# LPmini-Prototype_1_4.net
KiCad netlist of a schematic drawn in EAGLE
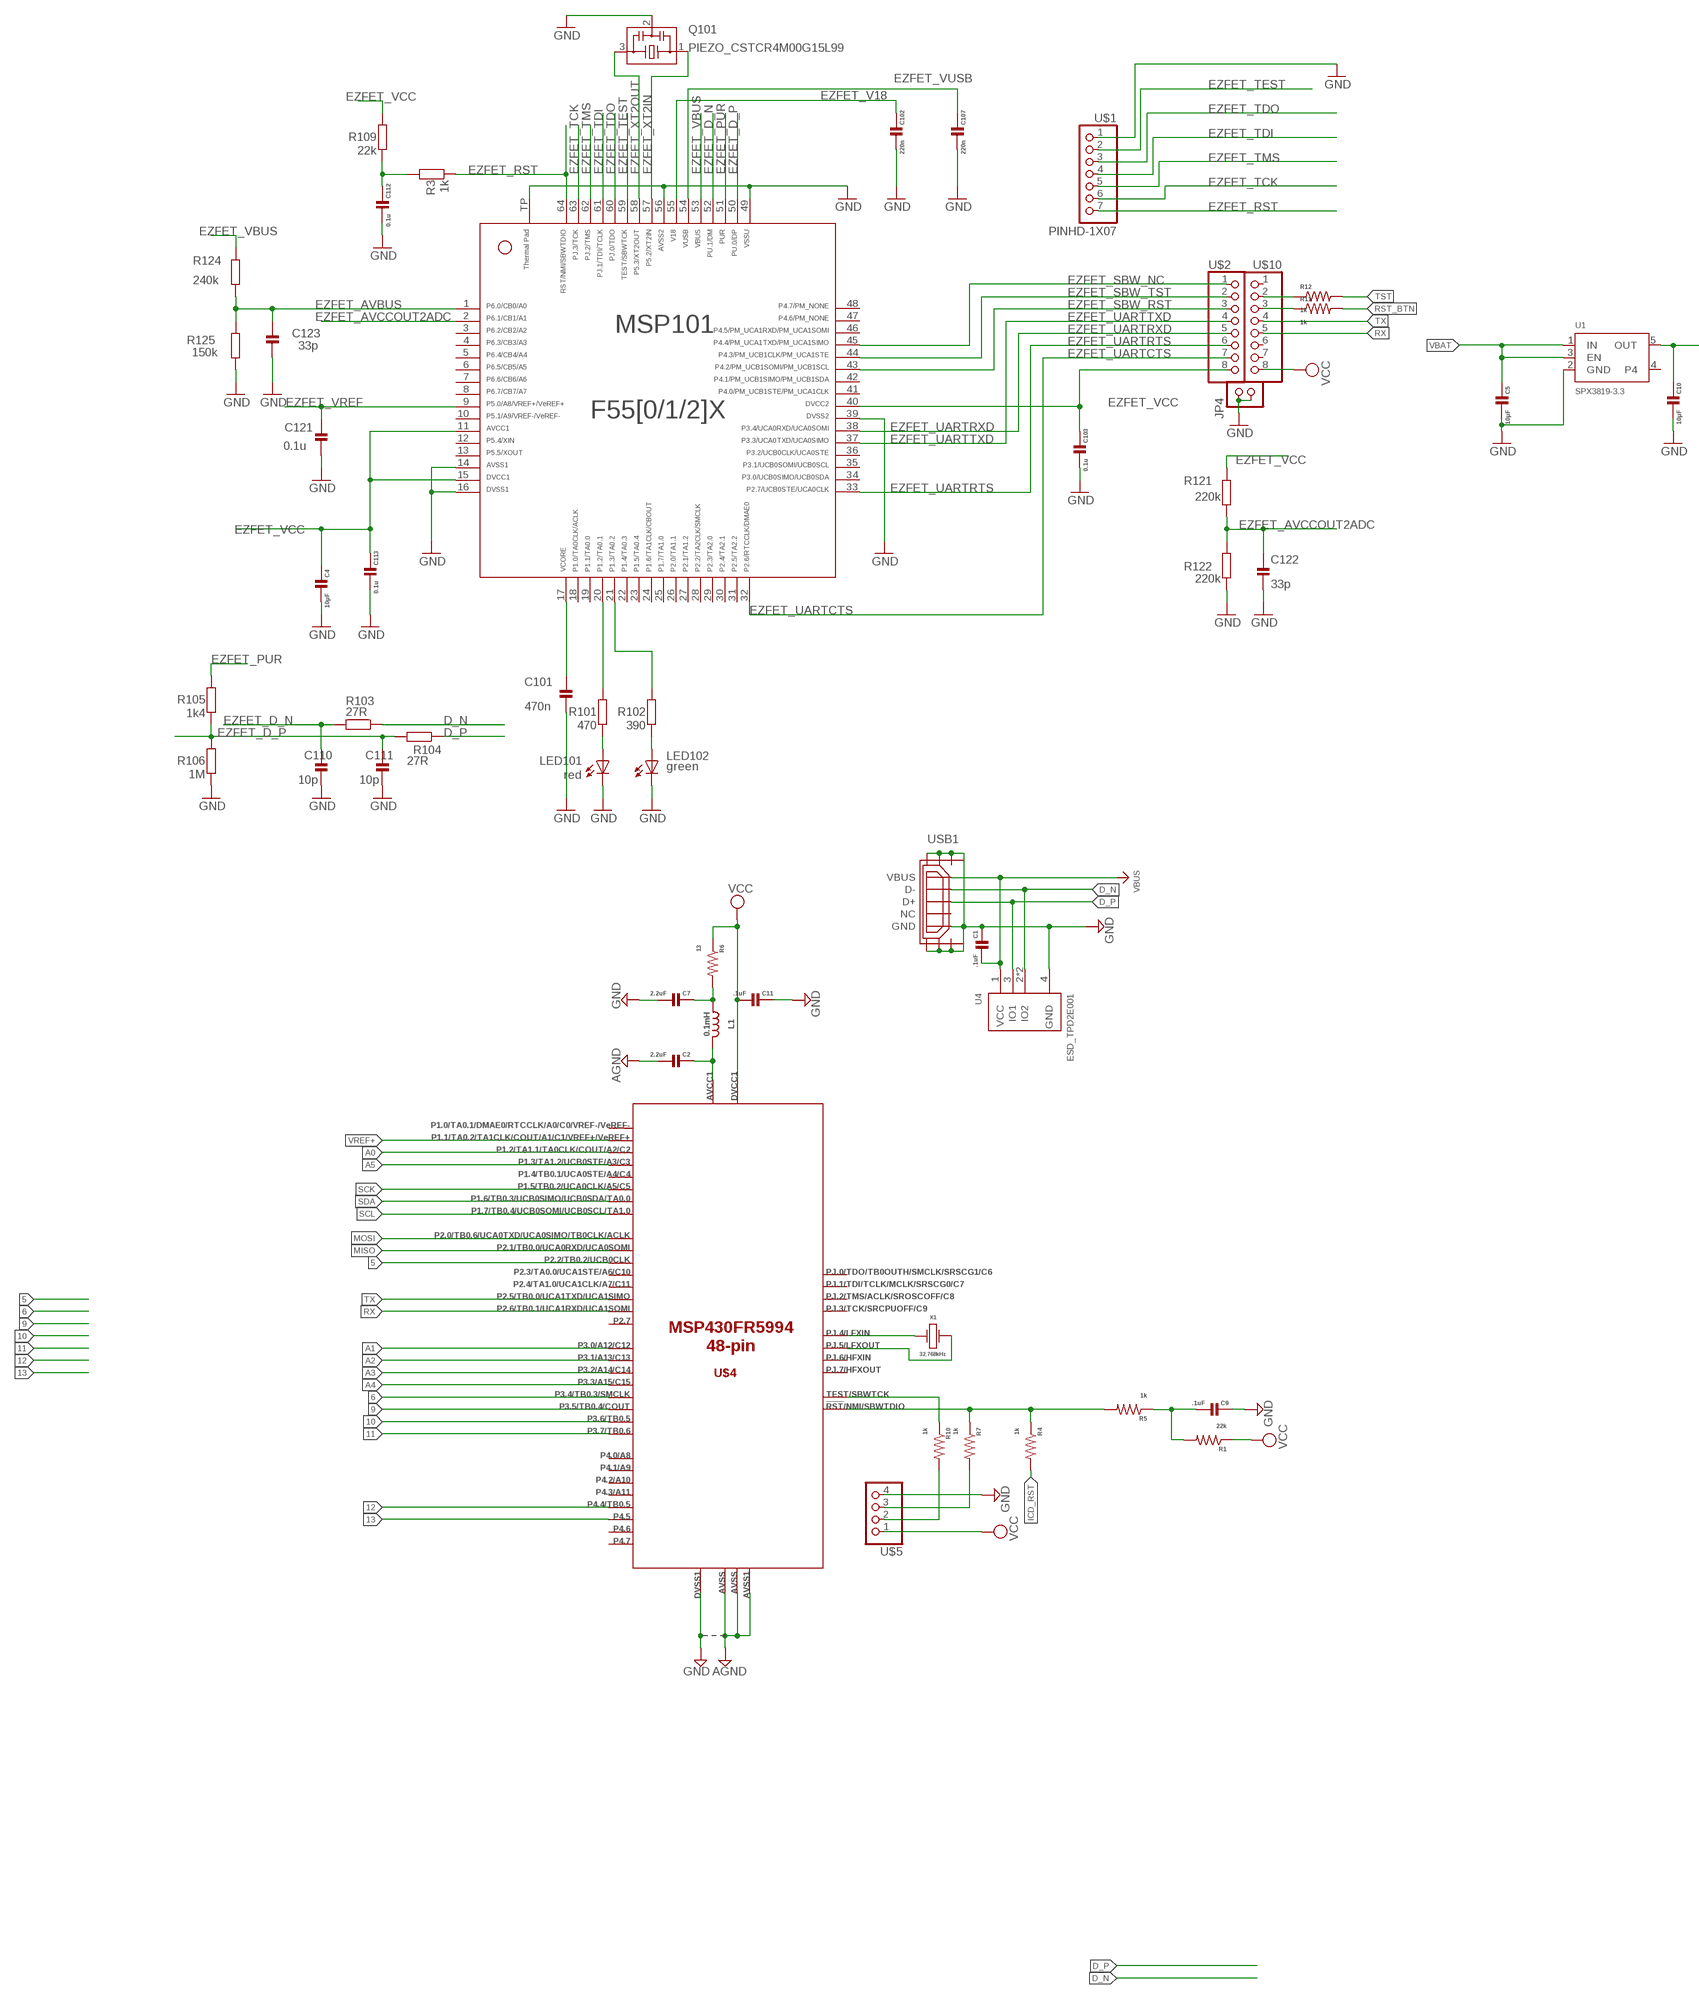
[diagram p0: schematic, sheet 1, part 1 of 2]
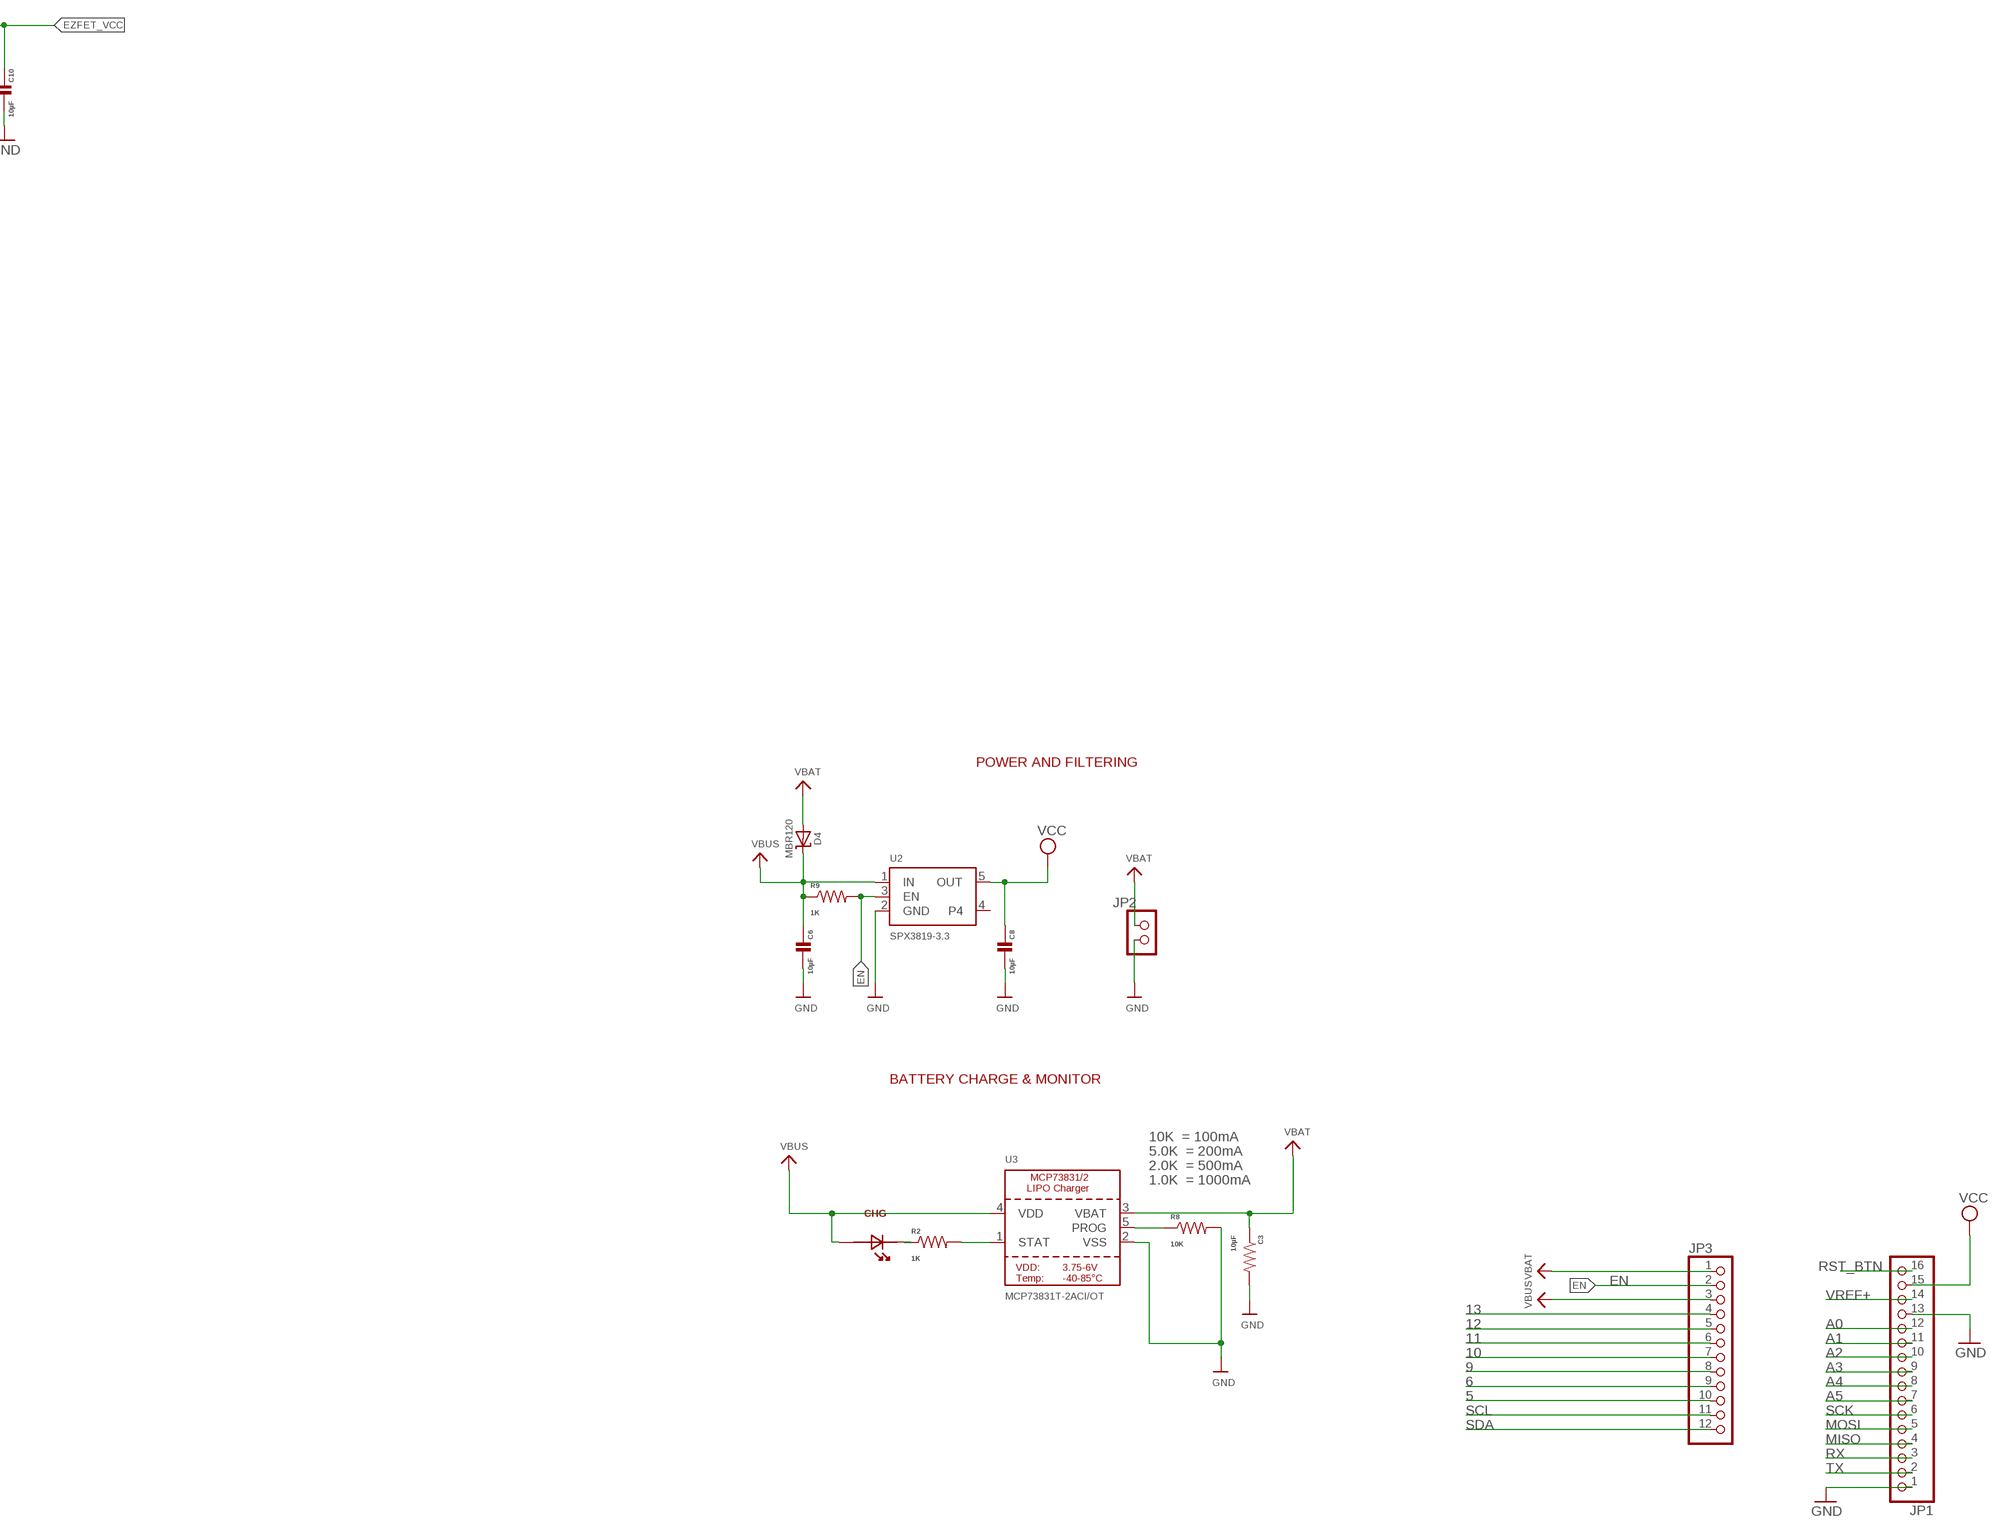
[diagram p1: schematic, sheet 1, part 2 of 2]

(export (version "E")
  (design (tool "Eeschema 10.0.6"))
  (components
    (comp (ref "C1")
      (value ".1uF")
      (footprint "eagle-import:C0402")
      (libsource (lib "eagle-import") (part "C-EUC0402"))
    )
    (comp (ref "C2")
      (value "2.2uF")
      (footprint "eagle-import:C0603")
      (libsource (lib "eagle-import") (part "C-EUC0603"))
    )
    (comp (ref "C3")
      (value "10µF")
      (footprint "eagle-import:R0402")
      (libsource (lib "eagle-import") (part "R-US_R0402"))
    )
    (comp (ref "C4")
      (value "10µF")
      (footprint "eagle-import:C0603")
      (libsource (lib "eagle-import") (part "C-EUC0603"))
    )
    (comp (ref "C5")
      (value "10µF")
      (footprint "eagle-import:C0603")
      (libsource (lib "eagle-import") (part "C-EUC0603"))
    )
    (comp (ref "C6")
      (value "10µF")
      (footprint "eagle-import:C0603")
      (libsource (lib "eagle-import") (part "C-EUC0603"))
    )
    (comp (ref "C7")
      (value "2.2uF")
      (footprint "eagle-import:C0603")
      (libsource (lib "eagle-import") (part "C-EUC0603"))
    )
    (comp (ref "C8")
      (value "10µF")
      (footprint "eagle-import:C0603")
      (libsource (lib "eagle-import") (part "C-EUC0603"))
    )
    (comp (ref "C9")
      (value ".1uF")
      (footprint "eagle-import:C0402")
      (libsource (lib "eagle-import") (part "C-EUC0402"))
    )
    (comp (ref "C10")
      (value "10µF")
      (footprint "eagle-import:C0603")
      (libsource (lib "eagle-import") (part "C-EUC0603"))
    )
    (comp (ref "C11")
      (value ".1uF")
      (footprint "eagle-import:C0402")
      (libsource (lib "eagle-import") (part "C-EUC0402"))
    )
    (comp (ref "C101")
      (value "470n")
      (footprint "eagle-import:C0402")
      (libsource (lib "eagle-import") (part "C-EUC0402"))
    )
    (comp (ref "C102")
      (value "220n")
      (footprint "eagle-import:C0402")
      (libsource (lib "eagle-import") (part "C-EUC0402"))
    )
    (comp (ref "C103")
      (value "0.1u")
      (footprint "eagle-import:C0402")
      (libsource (lib "eagle-import") (part "C-EUC0402"))
    )
    (comp (ref "C107")
      (value "220n")
      (footprint "eagle-import:C0402")
      (libsource (lib "eagle-import") (part "C-EUC0402"))
    )
    (comp (ref "C110")
      (value "10p")
      (footprint "eagle-import:C0402")
      (libsource (lib "eagle-import") (part "C-EUC0402"))
    )
    (comp (ref "C111")
      (value "10p")
      (footprint "eagle-import:C0402")
      (libsource (lib "eagle-import") (part "C-EUC0402"))
    )
    (comp (ref "C112")
      (value "0.1u")
      (footprint "eagle-import:C0402")
      (libsource (lib "eagle-import") (part "C-EUC0402"))
    )
    (comp (ref "C113")
      (value "0.1u")
      (footprint "eagle-import:C0402")
      (libsource (lib "eagle-import") (part "C-EUC0402"))
    )
    (comp (ref "C121")
      (value "0.1u")
      (footprint "eagle-import:C0402")
      (libsource (lib "eagle-import") (part "C-EUC0402"))
    )
    (comp (ref "C122")
      (value "33p")
      (footprint "eagle-import:C0402")
      (libsource (lib "eagle-import") (part "C-EUC0402"))
    )
    (comp (ref "C123")
      (value "33p")
      (footprint "eagle-import:C0402")
      (libsource (lib "eagle-import") (part "C-EUC0402"))
    )
    (comp (ref "CHG")
      (value "ORANGE")
      (footprint "eagle-import:LED_0603")
      (libsource (lib "eagle-import") (part "LED0603"))
    )
    (comp (ref "D4")
      (value "MBR120")
      (footprint "eagle-import:SOD-123")
      (libsource (lib "eagle-import") (part "DIODE-SCHOTTKYSOD-123"))
    )
    (comp (ref "JP1")
      (value "HEADER-1X16ROUND")
      (footprint "eagle-import:1X16_ROUND")
      (libsource (lib "eagle-import") (part "HEADER-1X16ROUND"))
    )
    (comp (ref "JP2")
      (value "0_JOSEPH_PINHD-1X2END")
      (footprint "eagle-import:0_JOSEPH_1X02-END")
      (libsource (lib "eagle-import") (part "0_JOSEPH_PINHD-1X2END"))
    )
    (comp (ref "JP3")
      (value "HEADER-1X12")
      (footprint "eagle-import:1X12_ROUND")
      (libsource (lib "eagle-import") (part "HEADER-1X12"))
    )
    (comp (ref "JP4")
      (value "0_JOSEPH_PINHD-1X2SMALL")
      (footprint "eagle-import:0_JOSEPH_1X02-SMALL")
      (libsource (lib "eagle-import") (part "0_JOSEPH_PINHD-1X2SMALL"))
    )
    (comp (ref "L1")
      (value "0.1mH")
      (footprint "eagle-import:RCL_R0805")
      (libsource (lib "eagle-import") (part "SMD_INDUCT0805"))
    )
    (comp (ref "LED101")
      (value "red")
      (footprint "eagle-import:CHIP-LED0603")
      (libsource (lib "eagle-import") (part "LEDCHIP-LED0603"))
    )
    (comp (ref "LED102")
      (value "green")
      (footprint "eagle-import:CHIP-LED0603")
      (libsource (lib "eagle-import") (part "LEDCHIP-LED0603"))
    )
    (comp (ref "MSP101")
      (value "MSP430F5528IRGC")
      (footprint "eagle-import:RGC64")
      (libsource (lib "eagle-import") (part "F55[0/1/2]X---RGC64"))
    )
    (comp (ref "Q101")
      (value "PIEZO_CSTCR4M00G15L99")
      (footprint "eagle-import:MURATA-FILTER_CSTCR")
      (fields (field (name "MPN") "CSTCR6M00G53-R0"))
      (libsource (lib "eagle-import") (part "MURATA-FILTER_CSTCR6M00G53Z"))
    )
    (comp (ref "R1")
      (value "22k")
      (footprint "eagle-import:R0402")
      (libsource (lib "eagle-import") (part "R-US_R0402"))
    )
    (comp (ref "R2")
      (value "1K")
      (footprint "eagle-import:R0402")
      (libsource (lib "eagle-import") (part "R-US_R0402"))
    )
    (comp (ref "R3")
      (value "1k")
      (footprint "eagle-import:R0402")
      (libsource (lib "eagle-import") (part "R-EU_R0402"))
    )
    (comp (ref "R4")
      (value "1k")
      (footprint "eagle-import:R0402")
      (libsource (lib "eagle-import") (part "R-US_R0402"))
    )
    (comp (ref "R5")
      (value "1k")
      (footprint "eagle-import:R0402")
      (libsource (lib "eagle-import") (part "R-US_R0402"))
    )
    (comp (ref "R6")
      (value "13")
      (footprint "eagle-import:R0402")
      (libsource (lib "eagle-import") (part "R-US_R0402"))
    )
    (comp (ref "R7")
      (value "1k")
      (footprint "eagle-import:R0402")
      (libsource (lib "eagle-import") (part "R-US_R0402"))
    )
    (comp (ref "R8")
      (value "10K")
      (footprint "eagle-import:R0402")
      (libsource (lib "eagle-import") (part "R-US_R0402"))
    )
    (comp (ref "R9")
      (value "1K")
      (footprint "eagle-import:R0402")
      (libsource (lib "eagle-import") (part "R-US_R0402"))
    )
    (comp (ref "R10")
      (value "1k")
      (footprint "eagle-import:R0402")
      (libsource (lib "eagle-import") (part "R-US_R0402"))
    )
    (comp (ref "R11")
      (value "1k")
      (footprint "eagle-import:R0402")
      (libsource (lib "eagle-import") (part "R-US_R0402"))
    )
    (comp (ref "R12")
      (value "1k")
      (footprint "eagle-import:R0402")
      (libsource (lib "eagle-import") (part "R-US_R0402"))
    )
    (comp (ref "R101")
      (value "470")
      (footprint "eagle-import:R0402")
      (libsource (lib "eagle-import") (part "R-EU_R0402"))
    )
    (comp (ref "R102")
      (value "390")
      (footprint "eagle-import:R0402")
      (libsource (lib "eagle-import") (part "R-EU_R0402"))
    )
    (comp (ref "R103")
      (value "27R")
      (footprint "eagle-import:R0402")
      (libsource (lib "eagle-import") (part "R-EU_R0402"))
    )
    (comp (ref "R104")
      (value "27R")
      (footprint "eagle-import:R0402")
      (libsource (lib "eagle-import") (part "R-EU_R0402"))
    )
    (comp (ref "R105")
      (value "1k4")
      (footprint "eagle-import:R0402")
      (libsource (lib "eagle-import") (part "R-EU_R0402"))
    )
    (comp (ref "R106")
      (value "1M")
      (footprint "eagle-import:R0402")
      (libsource (lib "eagle-import") (part "R-EU_R0402"))
    )
    (comp (ref "R109")
      (value "22k")
      (footprint "eagle-import:R0402")
      (libsource (lib "eagle-import") (part "R-EU_R0402"))
    )
    (comp (ref "R121")
      (value "220k")
      (footprint "eagle-import:R0402")
      (libsource (lib "eagle-import") (part "R-EU_R0402"))
    )
    (comp (ref "R122")
      (value "220k")
      (footprint "eagle-import:R0402")
      (libsource (lib "eagle-import") (part "R-EU_R0402"))
    )
    (comp (ref "R124")
      (value "240k")
      (footprint "eagle-import:R0402")
      (libsource (lib "eagle-import") (part "R-EU_R0402"))
    )
    (comp (ref "R125")
      (value "150k")
      (footprint "eagle-import:R0402")
      (libsource (lib "eagle-import") (part "R-EU_R0402"))
    )
    (comp (ref "U$1")
      (value "PINHD-1X07")
      (footprint "eagle-import:1X07")
      (libsource (lib "eagle-import") (part "PINHD-1X07"))
    )
    (comp (ref "U$2")
      (value "PINHD-1X08SMALL")
      (footprint "eagle-import:1X08-SMALL")
      (libsource (lib "eagle-import") (part "PINHD-1X08SMALL"))
    )
    (comp (ref "U$4")
      (value "MSP430FR5994-48PIN")
      (footprint "eagle-import:48QFN")
      (libsource (lib "eagle-import") (part "MSP430FR5994-48PIN"))
    )
    (comp (ref "U$5")
      (value "PINHD_1X4")
      (footprint "eagle-import:1X04")
      (libsource (lib "eagle-import") (part "PINHD_1X4"))
    )
    (comp (ref "U$10")
      (value "PINHD-1X08SMALL")
      (footprint "eagle-import:1X08-SMALL")
      (libsource (lib "eagle-import") (part "PINHD-1X08SMALL"))
    )
    (comp (ref "U1")
      (value "SPX3819-3.3")
      (footprint "eagle-import:SOT23-5")
      (libsource (lib "eagle-import") (part "VREG_SOT23-5"))
    )
    (comp (ref "U2")
      (value "SPX3819-3.3")
      (footprint "eagle-import:SOT23-5")
      (libsource (lib "eagle-import") (part "VREG_SOT23-5"))
    )
    (comp (ref "U3")
      (value "MCP73831T-2ACI/OT")
      (footprint "eagle-import:SOT23-5")
      (libsource (lib "eagle-import") (part "MCP73831/2"))
    )
    (comp (ref "U4")
      (value "ESD_TPD2E001")
      (footprint "eagle-import:PROJECT7264_TPD2E001-DRL")
      (libsource (lib "eagle-import") (part "ESD_TPD2E001"))
    )
    (comp (ref "USB1")
      (value "USB_CON-UPDATE_USB_MICRO_FLIPPED")
      (footprint "eagle-import:USB_CON-UPDATE_HIROSE-ZX62R-B-5P")
      (libsource (lib "eagle-import") (part "USB_CON-UPDATE_USB_MICRO_FLIPPED"))
    )
    (comp (ref "X1")
      (value "32.768kHz")
      (footprint "eagle-import:CRYSTAL_ABS05")
      (libsource (lib "eagle-import") (part "CRYSTALABS-05"))
    )
  )
  (nets
    (net (code "1") (name "/EZFET_AVBUS") (class "Default")
      (node (ref "C123") (pin "2") (pinfunction "2_2") (pintype "passive"))
      (node (ref "MSP101") (pin "1") (pinfunction "1_1") (pintype "bidirectional"))
      (node (ref "R124") (pin "2") (pinfunction "2_2") (pintype "passive"))
      (node (ref "R125") (pin "1") (pinfunction "1_1") (pintype "passive"))
    )
    (net (code "2") (name "/EZFET_AVCCOUT2ADC") (class "Default")
      (node (ref "C122") (pin "2") (pinfunction "2_2") (pintype "passive"))
      (node (ref "MSP101") (pin "2") (pinfunction "2_2") (pintype "bidirectional"))
      (node (ref "R121") (pin "2") (pinfunction "2_2") (pintype "passive"))
      (node (ref "R122") (pin "1") (pinfunction "1_1") (pintype "passive"))
    )
    (net (code "3") (name "/EZFET_D_N") (class "Default")
      (node (ref "C110") (pin "1") (pinfunction "1_1") (pintype "passive"))
      (node (ref "MSP101") (pin "52") (pinfunction "52_52") (pintype "bidirectional"))
      (node (ref "R103") (pin "2") (pinfunction "2_2") (pintype "passive"))
    )
    (net (code "4") (name "/EZFET_D_P") (class "Default")
      (node (ref "C111") (pin "1") (pinfunction "1_1") (pintype "passive"))
      (node (ref "MSP101") (pin "50") (pinfunction "50_50") (pintype "bidirectional"))
      (node (ref "R104") (pin "2") (pinfunction "2_2") (pintype "passive"))
      (node (ref "R105") (pin "1") (pinfunction "1_1") (pintype "passive"))
      (node (ref "R106") (pin "2") (pinfunction "2_2") (pintype "passive"))
    )
    (net (code "5") (name "/EZFET_PUR") (class "Default")
      (node (ref "MSP101") (pin "51") (pinfunction "51_51") (pintype "bidirectional"))
      (node (ref "R105") (pin "2") (pinfunction "2_2") (pintype "passive"))
    )
    (net (code "6") (name "/EZFET_RST") (class "Default")
      (node (ref "MSP101") (pin "64") (pinfunction "64_64") (pintype "bidirectional"))
      (node (ref "R3") (pin "1") (pinfunction "1_1") (pintype "passive"))
      (node (ref "U$1") (pin "7") (pinfunction "7_7") (pintype "passive"))
    )
    (net (code "7") (name "/EZFET_SBW_NC") (class "Default")
      (node (ref "MSP101") (pin "45") (pinfunction "45_45") (pintype "bidirectional"))
      (node (ref "U$2") (pin "1") (pinfunction "1_1") (pintype "passive"))
    )
    (net (code "8") (name "/EZFET_SBW_RST") (class "Default")
      (node (ref "MSP101") (pin "43") (pinfunction "43_43") (pintype "bidirectional"))
      (node (ref "U$2") (pin "3") (pinfunction "3_3") (pintype "passive"))
    )
    (net (code "9") (name "/EZFET_SBW_TST") (class "Default")
      (node (ref "MSP101") (pin "44") (pinfunction "44_44") (pintype "bidirectional"))
      (node (ref "U$2") (pin "2") (pinfunction "2_2") (pintype "passive"))
    )
    (net (code "10") (name "/EZFET_TCK") (class "Default")
      (node (ref "MSP101") (pin "63") (pinfunction "63_63") (pintype "bidirectional"))
      (node (ref "U$1") (pin "6") (pinfunction "6_6") (pintype "passive"))
    )
    (net (code "11") (name "/EZFET_TDI") (class "Default")
      (node (ref "MSP101") (pin "61") (pinfunction "61_61") (pintype "bidirectional"))
      (node (ref "U$1") (pin "4") (pinfunction "4_4") (pintype "passive"))
    )
    (net (code "12") (name "/EZFET_TDO") (class "Default")
      (node (ref "MSP101") (pin "60") (pinfunction "60_60") (pintype "bidirectional"))
      (node (ref "U$1") (pin "3") (pinfunction "3_3") (pintype "passive"))
    )
    (net (code "13") (name "/EZFET_TEST") (class "Default")
      (node (ref "MSP101") (pin "59") (pinfunction "59_59") (pintype "input"))
      (node (ref "U$1") (pin "2") (pinfunction "2_2") (pintype "passive"))
    )
    (net (code "14") (name "/EZFET_TMS") (class "Default")
      (node (ref "MSP101") (pin "62") (pinfunction "62_62") (pintype "bidirectional"))
      (node (ref "U$1") (pin "5") (pinfunction "5_5") (pintype "passive"))
    )
    (net (code "15") (name "/EZFET_UARTCTS") (class "Default")
      (node (ref "MSP101") (pin "32") (pinfunction "32_32") (pintype "bidirectional"))
      (node (ref "U$2") (pin "7") (pinfunction "7_7") (pintype "passive"))
    )
    (net (code "16") (name "/EZFET_UARTRTS") (class "Default")
      (node (ref "MSP101") (pin "33") (pinfunction "33_33") (pintype "bidirectional"))
      (node (ref "U$2") (pin "6") (pinfunction "6_6") (pintype "passive"))
    )
    (net (code "17") (name "/EZFET_UARTRXD") (class "Default")
      (node (ref "MSP101") (pin "38") (pinfunction "38_38") (pintype "bidirectional"))
      (node (ref "U$2") (pin "5") (pinfunction "5_5") (pintype "passive"))
    )
    (net (code "18") (name "/EZFET_UARTTXD") (class "Default")
      (node (ref "MSP101") (pin "37") (pinfunction "37_37") (pintype "bidirectional"))
      (node (ref "U$2") (pin "4") (pinfunction "4_4") (pintype "passive"))
    )
    (net (code "19") (name "/EZFET_V18") (class "Default")
      (node (ref "C102") (pin "1") (pinfunction "1_1") (pintype "passive"))
      (node (ref "MSP101") (pin "55") (pinfunction "55_55") (pintype "power_in"))
    )
    (net (code "20") (name "/EZFET_VBUS") (class "Default")
      (node (ref "MSP101") (pin "53") (pinfunction "53_53") (pintype "power_in"))
      (node (ref "R124") (pin "1") (pinfunction "1_1") (pintype "passive"))
    )
    (net (code "21") (name "/EZFET_VREF") (class "Default")
      (node (ref "C121") (pin "1") (pinfunction "1_1") (pintype "passive"))
      (node (ref "MSP101") (pin "9") (pinfunction "9_9") (pintype "bidirectional"))
    )
    (net (code "22") (name "/EZFET_VUSB") (class "Default")
      (node (ref "C107") (pin "1") (pinfunction "1_1") (pintype "passive"))
      (node (ref "MSP101") (pin "54") (pinfunction "54_54") (pintype "power_in"))
    )
    (net (code "23") (name "/EZFET_XT2IN") (class "Default")
      (node (ref "MSP101") (pin "57") (pinfunction "57_57") (pintype "bidirectional"))
      (node (ref "Q101") (pin "1") (pinfunction "1_1") (pintype "passive"))
    )
    (net (code "24") (name "/EZFET_XT2OUT") (class "Default")
      (node (ref "MSP101") (pin "58") (pinfunction "58_58") (pintype "bidirectional"))
      (node (ref "Q101") (pin "3") (pinfunction "3_3") (pintype "passive"))
    )
    (net (code "25") (name "5") (class "Default")
      (node (ref "JP3") (pin "10") (pinfunction "10_10") (pintype "passive"))
      (node (ref "U$4") (pin "26") (pinfunction "26_26") (pintype "bidirectional"))
    )
    (net (code "26") (name "6") (class "Default")
      (node (ref "JP3") (pin "9") (pinfunction "9_9") (pintype "passive"))
      (node (ref "U$4") (pin "27") (pinfunction "27_27") (pintype "bidirectional"))
    )
    (net (code "27") (name "9") (class "Default")
      (node (ref "JP3") (pin "8") (pinfunction "8_8") (pintype "passive"))
      (node (ref "U$4") (pin "28") (pinfunction "28_28") (pintype "bidirectional"))
    )
    (net (code "28") (name "10") (class "Default")
      (node (ref "JP3") (pin "7") (pinfunction "7_7") (pintype "passive"))
      (node (ref "U$4") (pin "29") (pinfunction "29_29") (pintype "bidirectional"))
    )
    (net (code "29") (name "11") (class "Default")
      (node (ref "JP3") (pin "6") (pinfunction "6_6") (pintype "passive"))
      (node (ref "U$4") (pin "30") (pinfunction "30_30") (pintype "bidirectional"))
    )
    (net (code "30") (name "12") (class "Default")
      (node (ref "JP3") (pin "5") (pinfunction "5_5") (pintype "passive"))
      (node (ref "U$4") (pin "33") (pinfunction "33_33") (pintype "bidirectional"))
    )
    (net (code "31") (name "13") (class "Default")
      (node (ref "JP3") (pin "4") (pinfunction "4_4") (pintype "passive"))
      (node (ref "U$4") (pin "34") (pinfunction "34_34") (pintype "bidirectional"))
    )
    (net (code "32") (name "A0") (class "Default")
      (node (ref "JP1") (pin "12") (pinfunction "12_12") (pintype "passive"))
      (node (ref "U$4") (pin "3") (pinfunction "3_3") (pintype "bidirectional"))
    )
    (net (code "33") (name "A1") (class "Default")
      (node (ref "JP1") (pin "11") (pinfunction "11_11") (pintype "passive"))
      (node (ref "U$4") (pin "4") (pinfunction "4_4") (pintype "bidirectional"))
    )
    (net (code "34") (name "A2") (class "Default")
      (node (ref "JP1") (pin "10") (pinfunction "10_10") (pintype "passive"))
      (node (ref "U$4") (pin "5") (pinfunction "5_5") (pintype "bidirectional"))
    )
    (net (code "35") (name "A3") (class "Default")
      (node (ref "JP1") (pin "9") (pinfunction "9_9") (pintype "passive"))
      (node (ref "U$4") (pin "6") (pinfunction "6_6") (pintype "bidirectional"))
    )
    (net (code "36") (name "A4") (class "Default")
      (node (ref "JP1") (pin "8") (pinfunction "8_8") (pintype "passive"))
      (node (ref "U$4") (pin "7") (pinfunction "7_7") (pintype "bidirectional"))
    )
    (net (code "37") (name "A5") (class "Default")
      (node (ref "JP1") (pin "7") (pinfunction "7_7") (pintype "passive"))
      (node (ref "U$4") (pin "9") (pinfunction "9_9") (pintype "bidirectional"))
    )
    (net (code "38") (name "AGND") (class "Default")
      (node (ref "C2") (pin "2") (pinfunction "2_2") (pintype "passive"))
      (node (ref "U$4") (pin "41") (pinfunction "41_41") (pintype "bidirectional"))
      (node (ref "U$4") (pin "44") (pinfunction "44_44") (pintype "bidirectional"))
      (node (ref "U$4") (pin "47") (pinfunction "47_47") (pintype "bidirectional"))
    )
    (net (code "39") (name "D_N") (class "Default")
      (node (ref "R103") (pin "1") (pinfunction "1_1") (pintype "passive"))
      (node (ref "U4") (pin "2") (pinfunction "IO2_2") (pintype "bidirectional"))
      (node (ref "U4") (pin "5") (pinfunction "IO2_5") (pintype "bidirectional"))
      (node (ref "USB1") (pin "D-") (pinfunction "D-_D-") (pintype "input"))
    )
    (net (code "40") (name "D_P") (class "Default")
      (node (ref "R104") (pin "1") (pinfunction "1_1") (pintype "passive"))
      (node (ref "U4") (pin "3") (pinfunction "IO1_3") (pintype "bidirectional"))
      (node (ref "USB1") (pin "D+") (pinfunction "D+_D+") (pintype "input"))
    )
    (net (code "41") (name "EN") (class "Default")
      (node (ref "JP3") (pin "2") (pinfunction "2_2") (pintype "passive"))
      (node (ref "R9") (pin "2") (pinfunction "2_2") (pintype "passive"))
      (node (ref "U2") (pin "3") (pinfunction "EN_3") (pintype "input"))
    )
    (net (code "42") (name "EZFET_VCC") (class "Default")
      (node (ref "C10") (pin "1") (pinfunction "1_1") (pintype "passive"))
      (node (ref "C103") (pin "1") (pinfunction "1_1") (pintype "passive"))
      (node (ref "C113") (pin "1") (pinfunction "1_1") (pintype "passive"))
      (node (ref "C4") (pin "1") (pinfunction "1_1") (pintype "passive"))
      (node (ref "MSP101") (pin "11") (pinfunction "11_11") (pintype "power_in"))
      (node (ref "MSP101") (pin "15") (pinfunction "15_15") (pintype "power_in"))
      (node (ref "MSP101") (pin "40") (pinfunction "40_40") (pintype "power_in"))
      (node (ref "R109") (pin "2") (pinfunction "2_2") (pintype "passive"))
      (node (ref "R121") (pin "1") (pinfunction "1_1") (pintype "passive"))
      (node (ref "U$2") (pin "8") (pinfunction "8_8") (pintype "passive"))
      (node (ref "U1") (pin "5") (pinfunction "OUT_5") (pintype "power_in"))
    )
    (net (code "43") (name "GND") (class "Default")
      (node (ref "C1") (pin "1") (pinfunction "1_1") (pintype "passive"))
      (node (ref "C10") (pin "2") (pinfunction "2_2") (pintype "passive"))
      (node (ref "C101") (pin "2") (pinfunction "2_2") (pintype "passive"))
      (node (ref "C102") (pin "2") (pinfunction "2_2") (pintype "passive"))
      (node (ref "C103") (pin "2") (pinfunction "2_2") (pintype "passive"))
      (node (ref "C107") (pin "2") (pinfunction "2_2") (pintype "passive"))
      (node (ref "C11") (pin "1") (pinfunction "1_1") (pintype "passive"))
      (node (ref "C110") (pin "2") (pinfunction "2_2") (pintype "passive"))
      (node (ref "C111") (pin "2") (pinfunction "2_2") (pintype "passive"))
      (node (ref "C112") (pin "2") (pinfunction "2_2") (pintype "passive"))
      (node (ref "C113") (pin "2") (pinfunction "2_2") (pintype "passive"))
      (node (ref "C121") (pin "2") (pinfunction "2_2") (pintype "passive"))
      (node (ref "C122") (pin "1") (pinfunction "1_1") (pintype "passive"))
      (node (ref "C123") (pin "1") (pinfunction "1_1") (pintype "passive"))
      (node (ref "C3") (pin "2") (pinfunction "2_2") (pintype "passive"))
      (node (ref "C4") (pin "2") (pinfunction "2_2") (pintype "passive"))
      (node (ref "C5") (pin "2") (pinfunction "2_2") (pintype "passive"))
      (node (ref "C6") (pin "2") (pinfunction "2_2") (pintype "passive"))
      (node (ref "C7") (pin "2") (pinfunction "2_2") (pintype "passive"))
      (node (ref "C8") (pin "2") (pinfunction "2_2") (pintype "passive"))
      (node (ref "C9") (pin "1") (pinfunction "1_1") (pintype "passive"))
      (node (ref "JP1") (pin "1") (pinfunction "1_1") (pintype "passive"))
      (node (ref "JP1") (pin "13") (pinfunction "13_13") (pintype "passive"))
      (node (ref "JP2") (pin "2") (pinfunction "2_2") (pintype "passive"))
      (node (ref "JP4") (pin "1") (pinfunction "1_1") (pintype "passive"))
      (node (ref "JP4") (pin "2") (pinfunction "2_2") (pintype "passive"))
      (node (ref "LED101") (pin "C") (pinfunction "C_C") (pintype "passive"))
      (node (ref "LED102") (pin "C") (pinfunction "C_C") (pintype "passive"))
      (node (ref "MSP101") (pin "14") (pinfunction "14_14") (pintype "power_in"))
      (node (ref "MSP101") (pin "16") (pinfunction "16_16") (pintype "power_in"))
      (node (ref "MSP101") (pin "39") (pinfunction "39_39") (pintype "power_in"))
      (node (ref "MSP101") (pin "49") (pinfunction "49_49") (pintype "power_in"))
      (node (ref "MSP101") (pin "56") (pinfunction "56_56") (pintype "power_in"))
      (node (ref "MSP101") (pin "TP") (pinfunction "TP_TP") (pintype "power_in"))
      (node (ref "Q101") (pin "2") (pinfunction "2_2") (pintype "passive"))
      (node (ref "R106") (pin "1") (pinfunction "1_1") (pintype "passive"))
      (node (ref "R122") (pin "2") (pinfunction "2_2") (pintype "passive"))
      (node (ref "R125") (pin "2") (pinfunction "2_2") (pintype "passive"))
      (node (ref "R8") (pin "2") (pinfunction "2_2") (pintype "passive"))
      (node (ref "U$1") (pin "1") (pinfunction "1_1") (pintype "passive"))
      (node (ref "U$4") (pin "36") (pinfunction "36_36") (pintype "bidirectional"))
      (node (ref "U$4") (pin "TAB") (pinfunction "36_TAB") (pintype "bidirectional"))
      (node (ref "U$5") (pin "4") (pinfunction "4_4") (pintype "passive"))
      (node (ref "U1") (pin "2") (pinfunction "GND_2") (pintype "power_in"))
      (node (ref "U2") (pin "2") (pinfunction "GND_2") (pintype "power_in"))
      (node (ref "U3") (pin "2") (pinfunction "VSS_2") (pintype "power_in"))
      (node (ref "U4") (pin "4") (pinfunction "GND_4") (pintype "power_in"))
      (node (ref "USB1") (pin "GND") (pinfunction "GND_GND") (pintype "input"))
      (node (ref "USB1") (pin "SHIELD1") (pinfunction "SHIELD1_SHIELD1") (pintype "bidirectional"))
      (node (ref "USB1") (pin "SHIELD2") (pinfunction "SHIELD2_SHIELD2") (pintype "bidirectional"))
      (node (ref "USB1") (pin "SHIELD3") (pinfunction "SHIELD3_SHIELD3") (pintype "bidirectional"))
      (node (ref "USB1") (pin "SHIELD4") (pinfunction "SHIELD4_SHIELD4") (pintype "bidirectional"))
      (node (ref "USB1") (pin "SHIELD5") (pinfunction "SHIELD5_SHIELD5") (pintype "bidirectional"))
      (node (ref "USB1") (pin "SHIELD6") (pinfunction "SHIELD6_SHIELD6") (pintype "bidirectional"))
    )
    (net (code "44") (name "ICD_RST") (class "Default")
      (node (ref "R4") (pin "2") (pinfunction "2_2") (pintype "passive"))
    )
    (net (code "45") (name "MISO") (class "Default")
      (node (ref "JP1") (pin "4") (pinfunction "4_4") (pintype "passive"))
      (node (ref "U$4") (pin "25") (pinfunction "25_25") (pintype "bidirectional"))
    )
    (net (code "46") (name "MOSI") (class "Default")
      (node (ref "JP1") (pin "5") (pinfunction "5_5") (pintype "passive"))
      (node (ref "U$4") (pin "24") (pinfunction "24_24") (pintype "bidirectional"))
    )
    (net (code "47") (name "Net-(C9-Pad2)") (class "Default")
      (node (ref "C9") (pin "2") (pinfunction "2_2") (pintype "passive"))
      (node (ref "R1") (pin "2") (pinfunction "2_2") (pintype "passive"))
      (node (ref "R5") (pin "1") (pinfunction "1_1") (pintype "passive"))
    )
    (net (code "48") (name "Net-(C101-Pad1)") (class "Default")
      (node (ref "C101") (pin "1") (pinfunction "1_1") (pintype "passive"))
      (node (ref "MSP101") (pin "17") (pinfunction "17_17") (pintype "power_in"))
    )
    (net (code "49") (name "Net-(C112-Pad1)") (class "Default")
      (node (ref "C112") (pin "1") (pinfunction "1_1") (pintype "passive"))
      (node (ref "R109") (pin "1") (pinfunction "1_1") (pintype "passive"))
      (node (ref "R3") (pin "2") (pinfunction "2_2") (pintype "passive"))
    )
    (net (code "50") (name "Net-(CHG-C)") (class "Default")
      (node (ref "CHG") (pin "K") (pinfunction "C_K") (pintype "bidirectional"))
      (node (ref "R2") (pin "1") (pinfunction "1_1") (pintype "passive"))
    )
    (net (code "51") (name "Net-(L1-P$1)") (class "Default")
      (node (ref "C2") (pin "1") (pinfunction "1_1") (pintype "passive"))
      (node (ref "L1") (pin "1") (pinfunction "P$1_1") (pintype "bidirectional"))
      (node (ref "U$4") (pin "48") (pinfunction "48_48") (pintype "bidirectional"))
    )
    (net (code "52") (name "Net-(L1-P$2)") (class "Default")
      (node (ref "C7") (pin "1") (pinfunction "1_1") (pintype "passive"))
      (node (ref "L1") (pin "2") (pinfunction "P$2_2") (pintype "bidirectional"))
      (node (ref "R6") (pin "2") (pinfunction "2_2") (pintype "passive"))
    )
    (net (code "53") (name "Net-(LED101-PadA)") (class "Default")
      (node (ref "LED101") (pin "A") (pinfunction "A_A") (pintype "passive"))
      (node (ref "R101") (pin "1") (pinfunction "1_1") (pintype "passive"))
    )
    (net (code "54") (name "Net-(LED102-PadA)") (class "Default")
      (node (ref "LED102") (pin "A") (pinfunction "A_A") (pintype "passive"))
      (node (ref "R102") (pin "1") (pinfunction "1_1") (pintype "passive"))
    )
    (net (code "55") (name "Net-(MSP101-Pad20)") (class "Default")
      (node (ref "MSP101") (pin "20") (pinfunction "20_20") (pintype "bidirectional"))
      (node (ref "R101") (pin "2") (pinfunction "2_2") (pintype "passive"))
    )
    (net (code "56") (name "Net-(MSP101-Pad21)") (class "Default")
      (node (ref "MSP101") (pin "21") (pinfunction "21_21") (pintype "bidirectional"))
      (node (ref "R102") (pin "2") (pinfunction "2_2") (pintype "passive"))
    )
    (net (code "57") (name "Net-(R4-Pad1)") (class "Default")
      (node (ref "R4") (pin "1") (pinfunction "1_1") (pintype "passive"))
      (node (ref "R5") (pin "2") (pinfunction "2_2") (pintype "passive"))
      (node (ref "R7") (pin "1") (pinfunction "1_1") (pintype "passive"))
      (node (ref "U$4") (pin "23") (pinfunction "23_23") (pintype "bidirectional"))
    )
    (net (code "58") (name "Net-(R10-Pad1)") (class "Default")
      (node (ref "R10") (pin "1") (pinfunction "1_1") (pintype "passive"))
      (node (ref "U$4") (pin "22") (pinfunction "22_22") (pintype "bidirectional"))
    )
    (net (code "59") (name "Net-(R11-Pad1)") (class "Default")
      (node (ref "R11") (pin "1") (pinfunction "1_1") (pintype "passive"))
      (node (ref "U$10") (pin "3") (pinfunction "3_3") (pintype "passive"))
    )
    (net (code "60") (name "Net-(R12-Pad1)") (class "Default")
      (node (ref "R12") (pin "1") (pinfunction "1_1") (pintype "passive"))
      (node (ref "U$10") (pin "2") (pinfunction "2_2") (pintype "passive"))
    )
    (net (code "61") (name "Net-(U$4-Pad45)") (class "Default")
      (node (ref "U$4") (pin "45") (pinfunction "45_45") (pintype "bidirectional"))
      (node (ref "X1") (pin "P$1") (pinfunction "P$1_P$1") (pintype "bidirectional"))
    )
    (net (code "62") (name "Net-(U$4-Pad46)") (class "Default")
      (node (ref "U$4") (pin "46") (pinfunction "46_46") (pintype "bidirectional"))
      (node (ref "X1") (pin "P$2") (pinfunction "P$2_P$2") (pintype "bidirectional"))
    )
    (net (code "63") (name "Net-(U3-PROG)") (class "Default")
      (node (ref "R8") (pin "1") (pinfunction "1_1") (pintype "passive"))
      (node (ref "U3") (pin "5") (pinfunction "PROG_5") (pintype "input"))
    )
    (net (code "64") (name "Net-(U3-STAT)") (class "Default")
      (node (ref "R2") (pin "2") (pinfunction "2_2") (pintype "passive"))
      (node (ref "U3") (pin "1") (pinfunction "STAT_1") (pintype "output"))
    )
    (net (code "65") (name "RST_BTN") (class "Default")
      (node (ref "JP1") (pin "16") (pinfunction "16_16") (pintype "passive"))
      (node (ref "R11") (pin "2") (pinfunction "2_2") (pintype "passive"))
      (node (ref "R7") (pin "2") (pinfunction "2_2") (pintype "passive"))
      (node (ref "U$5") (pin "3") (pinfunction "3_3") (pintype "passive"))
    )
    (net (code "66") (name "RX") (class "Default")
      (node (ref "JP1") (pin "3") (pinfunction "3_3") (pintype "passive"))
      (node (ref "U$10") (pin "5") (pinfunction "5_5") (pintype "passive"))
      (node (ref "U$4") (pin "21") (pinfunction "21_21") (pintype "bidirectional"))
    )
    (net (code "67") (name "SCK") (class "Default")
      (node (ref "JP1") (pin "6") (pinfunction "6_6") (pintype "passive"))
      (node (ref "U$4") (pin "11") (pinfunction "11_11") (pintype "bidirectional"))
    )
    (net (code "68") (name "SCL") (class "Default")
      (node (ref "JP3") (pin "11") (pinfunction "11_11") (pintype "passive"))
      (node (ref "U$4") (pin "32") (pinfunction "32_32") (pintype "bidirectional"))
    )
    (net (code "69") (name "SDA") (class "Default")
      (node (ref "JP3") (pin "12") (pinfunction "12_12") (pintype "passive"))
      (node (ref "U$4") (pin "31") (pinfunction "31_31") (pintype "bidirectional"))
    )
    (net (code "70") (name "TST") (class "Default")
      (node (ref "R10") (pin "2") (pinfunction "2_2") (pintype "passive"))
      (node (ref "R12") (pin "2") (pinfunction "2_2") (pintype "passive"))
      (node (ref "U$5") (pin "2") (pinfunction "2_2") (pintype "passive"))
    )
    (net (code "71") (name "TX") (class "Default")
      (node (ref "JP1") (pin "2") (pinfunction "2_2") (pintype "passive"))
      (node (ref "U$10") (pin "4") (pinfunction "4_4") (pintype "passive"))
      (node (ref "U$4") (pin "20") (pinfunction "20_20") (pintype "bidirectional"))
    )
    (net (code "72") (name "VBAT") (class "Default")
      (node (ref "C3") (pin "1") (pinfunction "1_1") (pintype "passive"))
      (node (ref "C5") (pin "1") (pinfunction "1_1") (pintype "passive"))
      (node (ref "D4") (pin "A") (pinfunction "A_A") (pintype "passive"))
      (node (ref "JP2") (pin "1") (pinfunction "1_1") (pintype "passive"))
      (node (ref "JP3") (pin "1") (pinfunction "1_1") (pintype "passive"))
      (node (ref "U1") (pin "1") (pinfunction "IN_1") (pintype "power_in"))
      (node (ref "U1") (pin "3") (pinfunction "EN_3") (pintype "input"))
      (node (ref "U3") (pin "3") (pinfunction "VBAT_3") (pintype "power_in"))
    )
    (net (code "73") (name "VBUS") (class "Default")
      (node (ref "C1") (pin "2") (pinfunction "2_2") (pintype "passive"))
      (node (ref "C6") (pin "1") (pinfunction "1_1") (pintype "passive"))
      (node (ref "CHG") (pin "A") (pinfunction "A_A") (pintype "bidirectional"))
      (node (ref "D4") (pin "C") (pinfunction "C_C") (pintype "passive"))
      (node (ref "JP3") (pin "3") (pinfunction "3_3") (pintype "passive"))
      (node (ref "R9") (pin "1") (pinfunction "1_1") (pintype "passive"))
      (node (ref "U2") (pin "1") (pinfunction "IN_1") (pintype "power_in"))
      (node (ref "U3") (pin "4") (pinfunction "VDD_4") (pintype "power_in"))
      (node (ref "U4") (pin "1") (pinfunction "VCC_1") (pintype "power_in"))
      (node (ref "USB1") (pin "VBUS") (pinfunction "VBUS_VBUS") (pintype "input"))
    )
    (net (code "74") (name "VCC") (class "Default")
      (node (ref "C11") (pin "2") (pinfunction "2_2") (pintype "passive"))
      (node (ref "C8") (pin "1") (pinfunction "1_1") (pintype "passive"))
      (node (ref "JP1") (pin "15") (pinfunction "15_15") (pintype "passive"))
      (node (ref "R1") (pin "1") (pinfunction "1_1") (pintype "passive"))
      (node (ref "R6") (pin "1") (pinfunction "1_1") (pintype "passive"))
      (node (ref "U$10") (pin "8") (pinfunction "8_8") (pintype "passive"))
      (node (ref "U$4") (pin "37") (pinfunction "37_37") (pintype "bidirectional"))
      (node (ref "U$5") (pin "1") (pinfunction "1_1") (pintype "passive"))
      (node (ref "U2") (pin "5") (pinfunction "OUT_5") (pintype "power_in"))
    )
    (net (code "75") (name "VREF+") (class "Default")
      (node (ref "JP1") (pin "14") (pinfunction "14_14") (pintype "passive"))
      (node (ref "U$4") (pin "2") (pinfunction "2_2") (pintype "bidirectional"))
    )
    (net (code "76") (name "unconnected-(MSP101-Pad3)") (class "Default")
      (node (ref "MSP101") (pin "3") (pinfunction "3_3") (pintype "bidirectional"))
    )
    (net (code "77") (name "unconnected-(MSP101-Pad4)") (class "Default")
      (node (ref "MSP101") (pin "4") (pinfunction "4_4") (pintype "bidirectional"))
    )
    (net (code "78") (name "unconnected-(MSP101-Pad5)") (class "Default")
      (node (ref "MSP101") (pin "5") (pinfunction "5_5") (pintype "bidirectional"))
    )
    (net (code "79") (name "unconnected-(MSP101-Pad6)") (class "Default")
      (node (ref "MSP101") (pin "6") (pinfunction "6_6") (pintype "bidirectional"))
    )
    (net (code "80") (name "unconnected-(MSP101-Pad7)") (class "Default")
      (node (ref "MSP101") (pin "7") (pinfunction "7_7") (pintype "bidirectional"))
    )
    (net (code "81") (name "unconnected-(MSP101-Pad8)") (class "Default")
      (node (ref "MSP101") (pin "8") (pinfunction "8_8") (pintype "bidirectional"))
    )
    (net (code "82") (name "unconnected-(MSP101-Pad10)") (class "Default")
      (node (ref "MSP101") (pin "10") (pinfunction "10_10") (pintype "bidirectional"))
    )
    (net (code "83") (name "unconnected-(MSP101-Pad12)") (class "Default")
      (node (ref "MSP101") (pin "12") (pinfunction "12_12") (pintype "bidirectional"))
    )
    (net (code "84") (name "unconnected-(MSP101-Pad13)") (class "Default")
      (node (ref "MSP101") (pin "13") (pinfunction "13_13") (pintype "bidirectional"))
    )
    (net (code "85") (name "unconnected-(MSP101-Pad18)") (class "Default")
      (node (ref "MSP101") (pin "18") (pinfunction "18_18") (pintype "bidirectional"))
    )
    (net (code "86") (name "unconnected-(MSP101-Pad19)") (class "Default")
      (node (ref "MSP101") (pin "19") (pinfunction "19_19") (pintype "bidirectional"))
    )
    (net (code "87") (name "unconnected-(MSP101-Pad22)") (class "Default")
      (node (ref "MSP101") (pin "22") (pinfunction "22_22") (pintype "bidirectional"))
    )
    (net (code "88") (name "unconnected-(MSP101-Pad23)") (class "Default")
      (node (ref "MSP101") (pin "23") (pinfunction "23_23") (pintype "bidirectional"))
    )
    (net (code "89") (name "unconnected-(MSP101-Pad24)") (class "Default")
      (node (ref "MSP101") (pin "24") (pinfunction "24_24") (pintype "bidirectional"))
    )
    (net (code "90") (name "unconnected-(MSP101-Pad25)") (class "Default")
      (node (ref "MSP101") (pin "25") (pinfunction "25_25") (pintype "bidirectional"))
    )
    (net (code "91") (name "unconnected-(MSP101-Pad26)") (class "Default")
      (node (ref "MSP101") (pin "26") (pinfunction "26_26") (pintype "bidirectional"))
    )
    (net (code "92") (name "unconnected-(MSP101-Pad27)") (class "Default")
      (node (ref "MSP101") (pin "27") (pinfunction "27_27") (pintype "bidirectional"))
    )
    (net (code "93") (name "unconnected-(MSP101-Pad28)") (class "Default")
      (node (ref "MSP101") (pin "28") (pinfunction "28_28") (pintype "bidirectional"))
    )
    (net (code "94") (name "unconnected-(MSP101-Pad29)") (class "Default")
      (node (ref "MSP101") (pin "29") (pinfunction "29_29") (pintype "bidirectional"))
    )
    (net (code "95") (name "unconnected-(MSP101-Pad30)") (class "Default")
      (node (ref "MSP101") (pin "30") (pinfunction "30_30") (pintype "bidirectional"))
    )
    (net (code "96") (name "unconnected-(MSP101-Pad31)") (class "Default")
      (node (ref "MSP101") (pin "31") (pinfunction "31_31") (pintype "bidirectional"))
    )
    (net (code "97") (name "unconnected-(MSP101-Pad34)") (class "Default")
      (node (ref "MSP101") (pin "34") (pinfunction "34_34") (pintype "bidirectional"))
    )
    (net (code "98") (name "unconnected-(MSP101-Pad35)") (class "Default")
      (node (ref "MSP101") (pin "35") (pinfunction "35_35") (pintype "bidirectional"))
    )
    (net (code "99") (name "unconnected-(MSP101-Pad36)") (class "Default")
      (node (ref "MSP101") (pin "36") (pinfunction "36_36") (pintype "bidirectional"))
    )
    (net (code "100") (name "unconnected-(MSP101-Pad41)") (class "Default")
      (node (ref "MSP101") (pin "41") (pinfunction "41_41") (pintype "bidirectional"))
    )
    (net (code "101") (name "unconnected-(MSP101-Pad42)") (class "Default")
      (node (ref "MSP101") (pin "42") (pinfunction "42_42") (pintype "bidirectional"))
    )
    (net (code "102") (name "unconnected-(MSP101-Pad46)") (class "Default")
      (node (ref "MSP101") (pin "46") (pinfunction "46_46") (pintype "bidirectional"))
    )
    (net (code "103") (name "unconnected-(MSP101-Pad47)") (class "Default")
      (node (ref "MSP101") (pin "47") (pinfunction "47_47") (pintype "bidirectional"))
    )
    (net (code "104") (name "unconnected-(MSP101-Pad48)") (class "Default")
      (node (ref "MSP101") (pin "48") (pinfunction "48_48") (pintype "bidirectional"))
    )
    (net (code "105") (name "unconnected-(U$4-Pad1)") (class "Default")
      (node (ref "U$4") (pin "1") (pinfunction "1_1") (pintype "bidirectional"))
    )
    (net (code "106") (name "unconnected-(U$4-Pad8)") (class "Default")
      (node (ref "U$4") (pin "8") (pinfunction "8_8") (pintype "bidirectional"))
    )
    (net (code "107") (name "unconnected-(U$4-Pad10)") (class "Default")
      (node (ref "U$4") (pin "10") (pinfunction "10_10") (pintype "bidirectional"))
    )
    (net (code "108") (name "unconnected-(U$4-Pad12)") (class "Default")
      (node (ref "U$4") (pin "12") (pinfunction "12_12") (pintype "bidirectional"))
    )
    (net (code "109") (name "unconnected-(U$4-Pad13)") (class "Default")
      (node (ref "U$4") (pin "13") (pinfunction "13_13") (pintype "bidirectional"))
    )
    (net (code "110") (name "unconnected-(U$4-Pad14)") (class "Default")
      (node (ref "U$4") (pin "14") (pinfunction "14_14") (pintype "bidirectional"))
    )
    (net (code "111") (name "unconnected-(U$4-Pad15)") (class "Default")
      (node (ref "U$4") (pin "15") (pinfunction "15_15") (pintype "bidirectional"))
    )
    (net (code "112") (name "unconnected-(U$4-Pad16)") (class "Default")
      (node (ref "U$4") (pin "16") (pinfunction "16_16") (pintype "bidirectional"))
    )
    (net (code "113") (name "unconnected-(U$4-Pad17)") (class "Default")
      (node (ref "U$4") (pin "17") (pinfunction "17_17") (pintype "bidirectional"))
    )
    (net (code "114") (name "unconnected-(U$4-Pad18)") (class "Default")
      (node (ref "U$4") (pin "18") (pinfunction "18_18") (pintype "bidirectional"))
    )
    (net (code "115") (name "unconnected-(U$4-Pad19)") (class "Default")
      (node (ref "U$4") (pin "19") (pinfunction "19_19") (pintype "bidirectional"))
    )
    (net (code "116") (name "unconnected-(U$4-Pad35)") (class "Default")
      (node (ref "U$4") (pin "35") (pinfunction "35_35") (pintype "bidirectional"))
    )
    (net (code "117") (name "unconnected-(U$4-Pad38)") (class "Default")
      (node (ref "U$4") (pin "38") (pinfunction "38_38") (pintype "bidirectional"))
    )
    (net (code "118") (name "unconnected-(U$4-Pad39)") (class "Default")
      (node (ref "U$4") (pin "39") (pinfunction "39_39") (pintype "bidirectional"))
    )
    (net (code "119") (name "unconnected-(U$4-Pad40)") (class "Default")
      (node (ref "U$4") (pin "40") (pinfunction "40_40") (pintype "bidirectional"))
    )
    (net (code "120") (name "unconnected-(U$4-Pad42)") (class "Default")
      (node (ref "U$4") (pin "42") (pinfunction "42_42") (pintype "bidirectional"))
    )
    (net (code "121") (name "unconnected-(U$4-Pad43)") (class "Default")
      (node (ref "U$4") (pin "43") (pinfunction "43_43") (pintype "bidirectional"))
    )
    (net (code "122") (name "unconnected-(U$10-Pad1)") (class "Default")
      (node (ref "U$10") (pin "1") (pinfunction "1_1") (pintype "passive"))
    )
    (net (code "123") (name "unconnected-(U$10-Pad6)") (class "Default")
      (node (ref "U$10") (pin "6") (pinfunction "6_6") (pintype "passive"))
    )
    (net (code "124") (name "unconnected-(U$10-Pad7)") (class "Default")
      (node (ref "U$10") (pin "7") (pinfunction "7_7") (pintype "passive"))
    )
    (net (code "125") (name "unconnected-(U1-P4-Pad4)") (class "Default")
      (node (ref "U1") (pin "4") (pinfunction "P4_4") (pintype "bidirectional"))
    )
    (net (code "126") (name "unconnected-(U2-P4-Pad4)") (class "Default")
      (node (ref "U2") (pin "4") (pinfunction "P4_4") (pintype "bidirectional"))
    )
    (net (code "127") (name "unconnected-(USB1-PadNC)") (class "Default")
      (node (ref "USB1") (pin "NC") (pinfunction "NC_NC") (pintype "input"))
    )
  )
)
